# IO_board-ha-v2.net
KiCad netlist of a schematic drawn in EAGLE
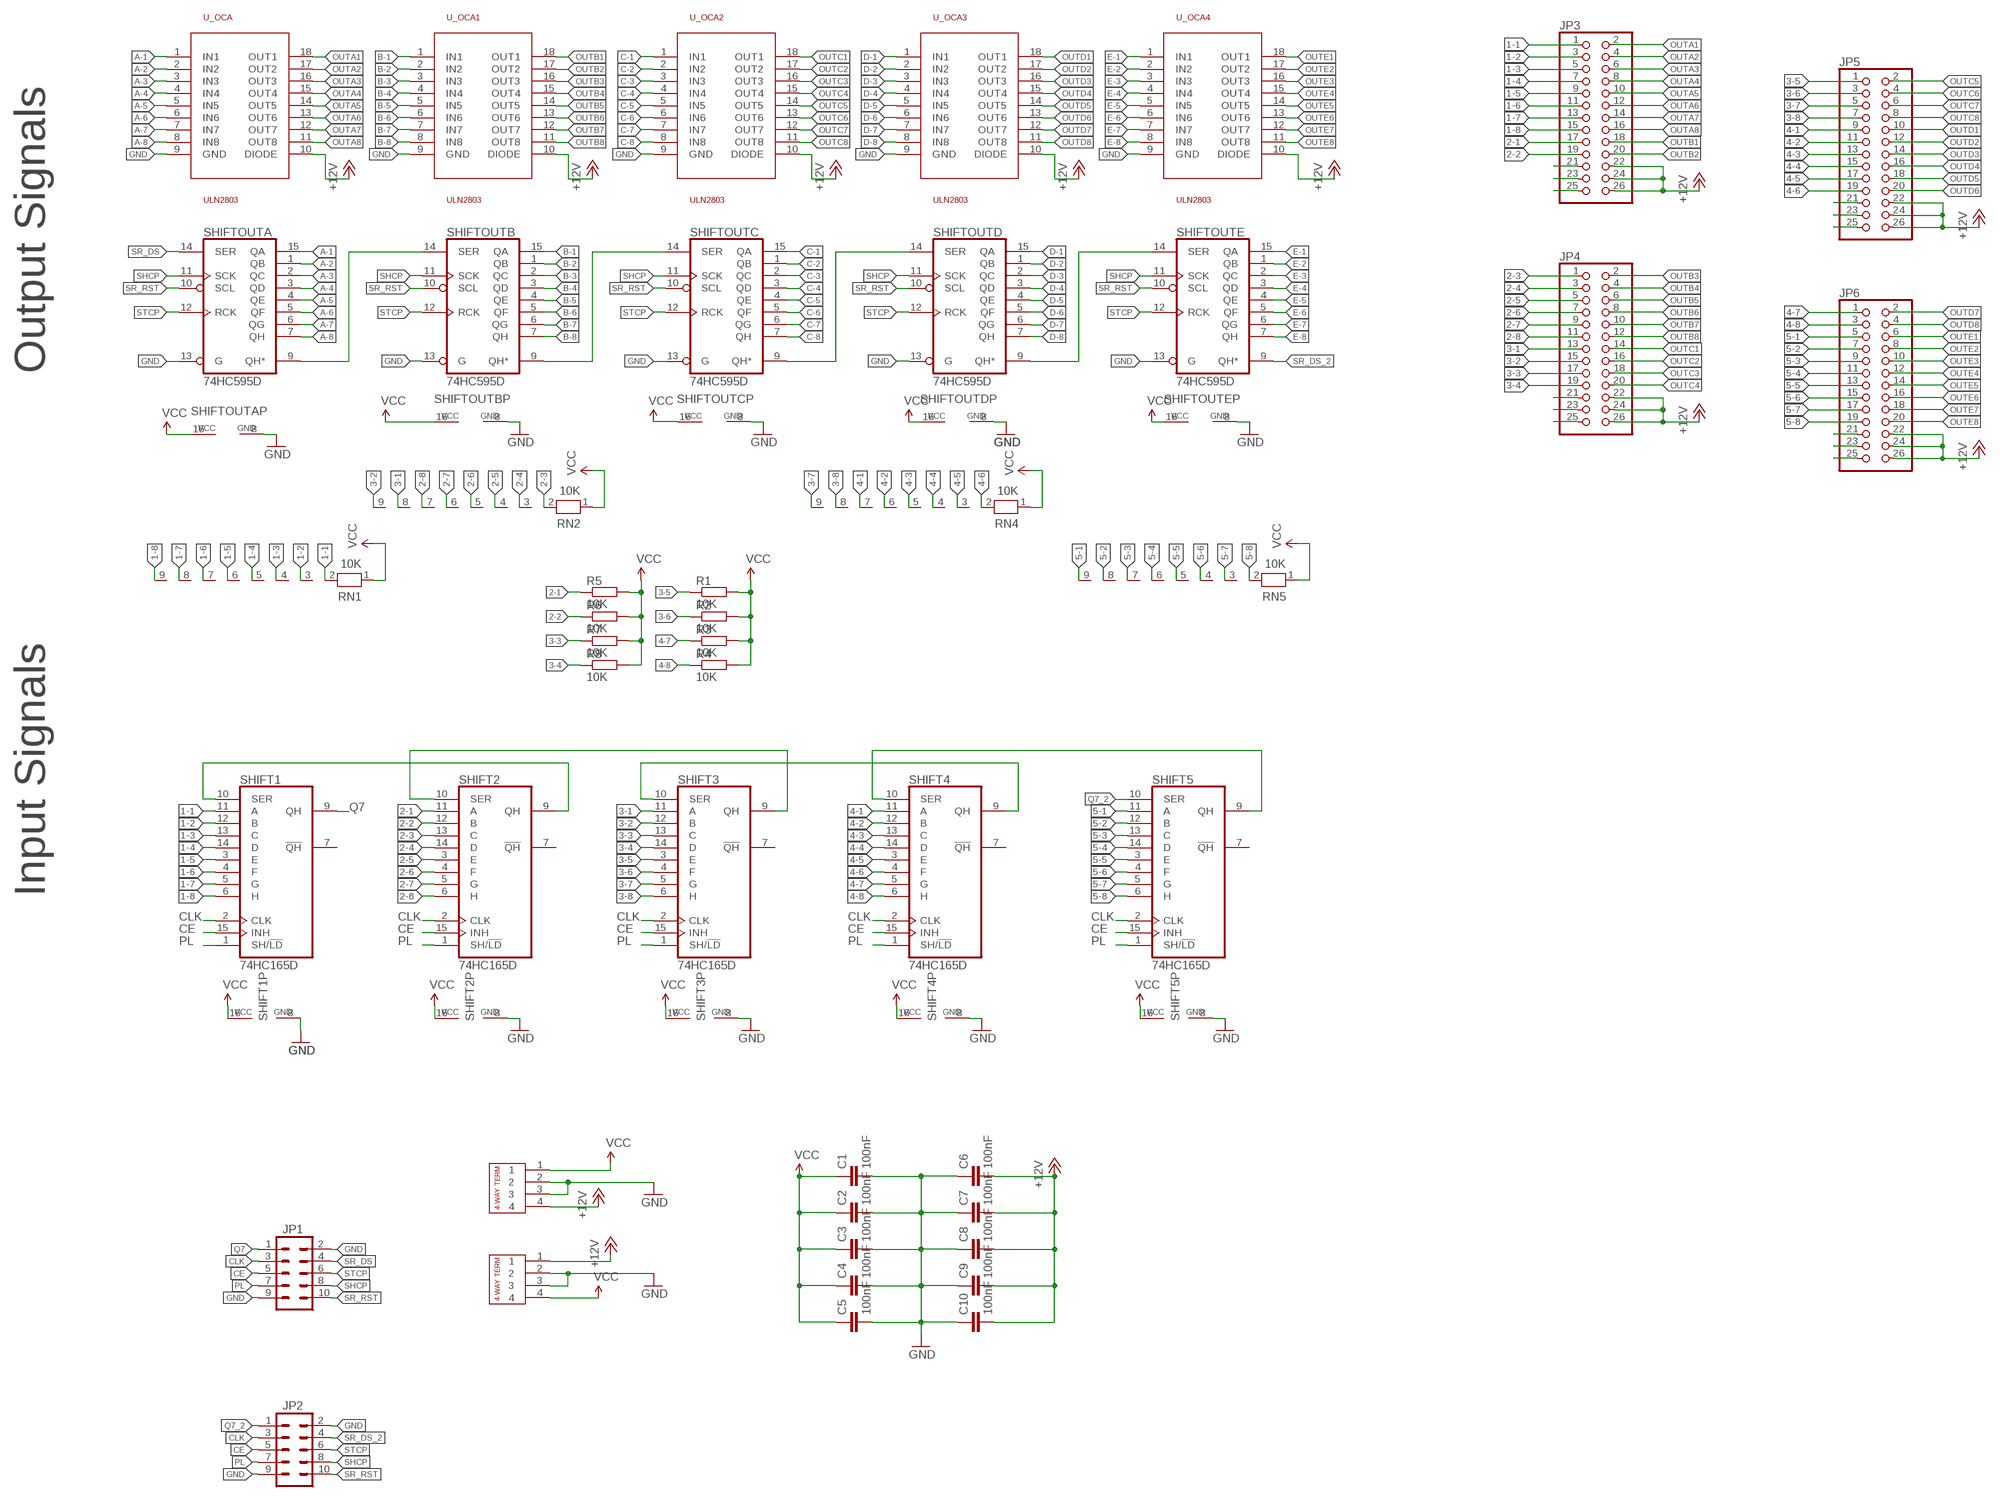
[diagram p0: schematic, sheet 1]

(export (version "E")
  (design (tool "Eeschema 10.0.6"))
  (components
    (comp (ref "C1")
      (value "100nF")
      (footprint "eagle-import:C0805")
      (libsource (lib "eagle-import") (part "C-EUC0805"))
    )
    (comp (ref "C2")
      (value "100nF")
      (footprint "eagle-import:C0805")
      (libsource (lib "eagle-import") (part "C-EUC0805"))
    )
    (comp (ref "C3")
      (value "100nF")
      (footprint "eagle-import:C0805")
      (libsource (lib "eagle-import") (part "C-EUC0805"))
    )
    (comp (ref "C4")
      (value "100nF")
      (footprint "eagle-import:C0805")
      (libsource (lib "eagle-import") (part "C-EUC0805"))
    )
    (comp (ref "C5")
      (value "100nF")
      (footprint "eagle-import:C0805")
      (libsource (lib "eagle-import") (part "C-EUC0805"))
    )
    (comp (ref "C6")
      (value "100nF")
      (footprint "eagle-import:C0805")
      (libsource (lib "eagle-import") (part "C-EUC0805"))
    )
    (comp (ref "C7")
      (value "100nF")
      (footprint "eagle-import:C0805")
      (libsource (lib "eagle-import") (part "C-EUC0805"))
    )
    (comp (ref "C8")
      (value "100nF")
      (footprint "eagle-import:C0805")
      (libsource (lib "eagle-import") (part "C-EUC0805"))
    )
    (comp (ref "C9")
      (value "100nF")
      (footprint "eagle-import:C0805")
      (libsource (lib "eagle-import") (part "C-EUC0805"))
    )
    (comp (ref "C10")
      (value "100nF")
      (footprint "eagle-import:C0805")
      (libsource (lib "eagle-import") (part "C-EUC0805"))
    )
    (comp (ref "J1")
      (value "4-PIN-CON-1759017")
      (footprint "eagle-import:4-PIN-CON-1759017")
      (libsource (lib "eagle-import") (part "4-PIN-CON-1759017"))
    )
    (comp (ref "J2")
      (value "4-PIN-CON-1759017")
      (footprint "eagle-import:4-PIN-CON-1759017")
      (libsource (lib "eagle-import") (part "4-PIN-CON-1759017"))
    )
    (comp (ref "JP1")
      (value "M05X2SHD")
      (footprint "eagle-import:2X5-SHROUDED")
      (libsource (lib "eagle-import") (part "M05X2SHD"))
    )
    (comp (ref "JP2")
      (value "M05X2SHD")
      (footprint "eagle-import:2X5-SHROUDED")
      (libsource (lib "eagle-import") (part "M05X2SHD"))
    )
    (comp (ref "JP3")
      (value "PINHD-2X13")
      (footprint "eagle-import:2X13")
      (libsource (lib "eagle-import") (part "PINHD-2X13"))
    )
    (comp (ref "JP4")
      (value "PINHD-2X13")
      (footprint "eagle-import:2X13")
      (libsource (lib "eagle-import") (part "PINHD-2X13"))
    )
    (comp (ref "JP5")
      (value "PINHD-2X13")
      (footprint "eagle-import:2X13")
      (libsource (lib "eagle-import") (part "PINHD-2X13"))
    )
    (comp (ref "JP6")
      (value "PINHD-2X13")
      (footprint "eagle-import:2X13")
      (libsource (lib "eagle-import") (part "PINHD-2X13"))
    )
    (comp (ref "R1")
      (value "10K")
      (footprint "eagle-import:R0603")
      (libsource (lib "eagle-import") (part "R-EU_R0603"))
    )
    (comp (ref "R2")
      (value "10K")
      (footprint "eagle-import:R0603")
      (libsource (lib "eagle-import") (part "R-EU_R0603"))
    )
    (comp (ref "R3")
      (value "10K")
      (footprint "eagle-import:R0603")
      (libsource (lib "eagle-import") (part "R-EU_R0603"))
    )
    (comp (ref "R4")
      (value "10K")
      (footprint "eagle-import:R0603")
      (libsource (lib "eagle-import") (part "R-EU_R0603"))
    )
    (comp (ref "R5")
      (value "10K")
      (footprint "eagle-import:R0603")
      (libsource (lib "eagle-import") (part "R-EU_R0603"))
    )
    (comp (ref "R6")
      (value "10K")
      (footprint "eagle-import:R0603")
      (libsource (lib "eagle-import") (part "R-EU_R0603"))
    )
    (comp (ref "R7")
      (value "10K")
      (footprint "eagle-import:R0603")
      (libsource (lib "eagle-import") (part "R-EU_R0603"))
    )
    (comp (ref "R8")
      (value "10K")
      (footprint "eagle-import:R0603")
      (libsource (lib "eagle-import") (part "R-EU_R0603"))
    )
    (comp (ref "RN1")
      (value "10K")
      (footprint "eagle-import:RN-9")
      (libsource (lib "eagle-import") (part "RN08"))
    )
    (comp (ref "RN2")
      (value "10K")
      (footprint "eagle-import:RN-9")
      (libsource (lib "eagle-import") (part "RN08"))
    )
    (comp (ref "RN4")
      (value "10K")
      (footprint "eagle-import:RN-9")
      (libsource (lib "eagle-import") (part "RN08"))
    )
    (comp (ref "RN5")
      (value "10K")
      (footprint "eagle-import:RN-9")
      (libsource (lib "eagle-import") (part "RN08"))
    )
    (comp (ref "SHIFT1")
      (value "74HC165D")
      (footprint "eagle-import:SO16")
      (libsource (lib "eagle-import") (part "74165DHC"))
    )
    (comp (ref "SHIFT2")
      (value "74HC165D")
      (footprint "eagle-import:SO16")
      (libsource (lib "eagle-import") (part "74165DHC"))
    )
    (comp (ref "SHIFT3")
      (value "74HC165D")
      (footprint "eagle-import:SO16")
      (libsource (lib "eagle-import") (part "74165DHC"))
    )
    (comp (ref "SHIFT4")
      (value "74HC165D")
      (footprint "eagle-import:SO16")
      (libsource (lib "eagle-import") (part "74165DHC"))
    )
    (comp (ref "SHIFT5")
      (value "74HC165D")
      (footprint "eagle-import:SO16")
      (libsource (lib "eagle-import") (part "74165DHC"))
    )
    (comp (ref "SHIFTOUTA")
      (value "74HC595D")
      (footprint "eagle-import:SO16")
      (libsource (lib "eagle-import") (part "74595DHC"))
    )
    (comp (ref "SHIFTOUTB")
      (value "74HC595D")
      (footprint "eagle-import:SO16")
      (libsource (lib "eagle-import") (part "74595DHC"))
    )
    (comp (ref "SHIFTOUTC")
      (value "74HC595D")
      (footprint "eagle-import:SO16")
      (libsource (lib "eagle-import") (part "74595DHC"))
    )
    (comp (ref "SHIFTOUTD")
      (value "74HC595D")
      (footprint "eagle-import:SO16")
      (libsource (lib "eagle-import") (part "74595DHC"))
    )
    (comp (ref "SHIFTOUTE")
      (value "74HC595D")
      (footprint "eagle-import:SO16")
      (libsource (lib "eagle-import") (part "74595DHC"))
    )
    (comp (ref "U_OCA")
      (value "ULN2803")
      (footprint "eagle-import:SO18L")
      (libsource (lib "eagle-import") (part "ULN2803"))
    )
    (comp (ref "U_OCA1")
      (value "ULN2803")
      (footprint "eagle-import:SO18L")
      (libsource (lib "eagle-import") (part "ULN2803"))
    )
    (comp (ref "U_OCA2")
      (value "ULN2803")
      (footprint "eagle-import:SO18L")
      (libsource (lib "eagle-import") (part "ULN2803"))
    )
    (comp (ref "U_OCA3")
      (value "ULN2803")
      (footprint "eagle-import:SO18L")
      (libsource (lib "eagle-import") (part "ULN2803"))
    )
    (comp (ref "U_OCA4")
      (value "ULN2803")
      (footprint "eagle-import:SO18L")
      (libsource (lib "eagle-import") (part "ULN2803"))
    )
  )
  (nets
    (net (code "1") (name "+12V") (class "Default")
      (node (ref "C10") (pin "2") (pinfunction "2_2") (pintype "passive"))
      (node (ref "C6") (pin "2") (pinfunction "2_2") (pintype "passive"))
      (node (ref "C7") (pin "2") (pinfunction "2_2") (pintype "passive"))
      (node (ref "C8") (pin "2") (pinfunction "2_2") (pintype "passive"))
      (node (ref "C9") (pin "2") (pinfunction "2_2") (pintype "passive"))
      (node (ref "J1") (pin "4") (pinfunction "4_4") (pintype "bidirectional"))
      (node (ref "J2") (pin "1") (pinfunction "1_1") (pintype "bidirectional"))
      (node (ref "JP3") (pin "22") (pinfunction "22_22") (pintype "passive"))
      (node (ref "JP3") (pin "24") (pinfunction "24_24") (pintype "passive"))
      (node (ref "JP3") (pin "26") (pinfunction "26_26") (pintype "passive"))
      (node (ref "JP4") (pin "22") (pinfunction "22_22") (pintype "passive"))
      (node (ref "JP4") (pin "24") (pinfunction "24_24") (pintype "passive"))
      (node (ref "JP4") (pin "26") (pinfunction "26_26") (pintype "passive"))
      (node (ref "JP5") (pin "22") (pinfunction "22_22") (pintype "passive"))
      (node (ref "JP5") (pin "24") (pinfunction "24_24") (pintype "passive"))
      (node (ref "JP5") (pin "26") (pinfunction "26_26") (pintype "passive"))
      (node (ref "JP6") (pin "22") (pinfunction "22_22") (pintype "passive"))
      (node (ref "JP6") (pin "24") (pinfunction "24_24") (pintype "passive"))
      (node (ref "JP6") (pin "26") (pinfunction "26_26") (pintype "passive"))
      (node (ref "U_OCA") (pin "10") (pinfunction "DIODE_10") (pintype "power_in"))
      (node (ref "U_OCA1") (pin "10") (pinfunction "DIODE_10") (pintype "power_in"))
      (node (ref "U_OCA2") (pin "10") (pinfunction "DIODE_10") (pintype "power_in"))
      (node (ref "U_OCA3") (pin "10") (pinfunction "DIODE_10") (pintype "power_in"))
      (node (ref "U_OCA4") (pin "10") (pinfunction "DIODE_10") (pintype "power_in"))
    )
    (net (code "2") (name "1-1") (class "Default")
      (node (ref "JP3") (pin "1") (pinfunction "1_1") (pintype "passive"))
      (node (ref "RN1") (pin "2") (pinfunction "2_2") (pintype "passive"))
      (node (ref "SHIFT1") (pin "11") (pinfunction "A_11") (pintype "input"))
    )
    (net (code "3") (name "1-2") (class "Default")
      (node (ref "JP3") (pin "3") (pinfunction "3_3") (pintype "passive"))
      (node (ref "RN1") (pin "3") (pinfunction "3_3") (pintype "passive"))
      (node (ref "SHIFT1") (pin "12") (pinfunction "B_12") (pintype "input"))
    )
    (net (code "4") (name "1-3") (class "Default")
      (node (ref "JP3") (pin "5") (pinfunction "5_5") (pintype "passive"))
      (node (ref "RN1") (pin "4") (pinfunction "4_4") (pintype "passive"))
      (node (ref "SHIFT1") (pin "13") (pinfunction "C_13") (pintype "input"))
    )
    (net (code "5") (name "1-4") (class "Default")
      (node (ref "JP3") (pin "7") (pinfunction "7_7") (pintype "passive"))
      (node (ref "RN1") (pin "5") (pinfunction "5_5") (pintype "passive"))
      (node (ref "SHIFT1") (pin "14") (pinfunction "D_14") (pintype "input"))
    )
    (net (code "6") (name "1-5") (class "Default")
      (node (ref "JP3") (pin "9") (pinfunction "9_9") (pintype "passive"))
      (node (ref "RN1") (pin "6") (pinfunction "6_6") (pintype "passive"))
      (node (ref "SHIFT1") (pin "3") (pinfunction "E_3") (pintype "input"))
    )
    (net (code "7") (name "1-6") (class "Default")
      (node (ref "JP3") (pin "11") (pinfunction "11_11") (pintype "passive"))
      (node (ref "RN1") (pin "7") (pinfunction "7_7") (pintype "passive"))
      (node (ref "SHIFT1") (pin "4") (pinfunction "F_4") (pintype "input"))
    )
    (net (code "8") (name "1-7") (class "Default")
      (node (ref "JP3") (pin "13") (pinfunction "13_13") (pintype "passive"))
      (node (ref "RN1") (pin "8") (pinfunction "8_8") (pintype "passive"))
      (node (ref "SHIFT1") (pin "5") (pinfunction "G_5") (pintype "input"))
    )
    (net (code "9") (name "1-8") (class "Default")
      (node (ref "JP3") (pin "15") (pinfunction "15_15") (pintype "passive"))
      (node (ref "RN1") (pin "9") (pinfunction "9_9") (pintype "passive"))
      (node (ref "SHIFT1") (pin "6") (pinfunction "H_6") (pintype "input"))
    )
    (net (code "10") (name "2-1") (class "Default")
      (node (ref "JP3") (pin "17") (pinfunction "17_17") (pintype "passive"))
      (node (ref "R5") (pin "1") (pinfunction "1_1") (pintype "passive"))
      (node (ref "SHIFT2") (pin "11") (pinfunction "A_11") (pintype "input"))
    )
    (net (code "11") (name "2-2") (class "Default")
      (node (ref "JP3") (pin "19") (pinfunction "19_19") (pintype "passive"))
      (node (ref "R6") (pin "1") (pinfunction "1_1") (pintype "passive"))
      (node (ref "SHIFT2") (pin "12") (pinfunction "B_12") (pintype "input"))
    )
    (net (code "12") (name "2-3") (class "Default")
      (node (ref "JP4") (pin "1") (pinfunction "1_1") (pintype "passive"))
      (node (ref "RN2") (pin "2") (pinfunction "2_2") (pintype "passive"))
      (node (ref "SHIFT2") (pin "13") (pinfunction "C_13") (pintype "input"))
    )
    (net (code "13") (name "2-4") (class "Default")
      (node (ref "JP4") (pin "3") (pinfunction "3_3") (pintype "passive"))
      (node (ref "RN2") (pin "3") (pinfunction "3_3") (pintype "passive"))
      (node (ref "SHIFT2") (pin "14") (pinfunction "D_14") (pintype "input"))
    )
    (net (code "14") (name "2-5") (class "Default")
      (node (ref "JP4") (pin "5") (pinfunction "5_5") (pintype "passive"))
      (node (ref "RN2") (pin "4") (pinfunction "4_4") (pintype "passive"))
      (node (ref "SHIFT2") (pin "3") (pinfunction "E_3") (pintype "input"))
    )
    (net (code "15") (name "2-6") (class "Default")
      (node (ref "JP4") (pin "7") (pinfunction "7_7") (pintype "passive"))
      (node (ref "RN2") (pin "5") (pinfunction "5_5") (pintype "passive"))
      (node (ref "SHIFT2") (pin "4") (pinfunction "F_4") (pintype "input"))
    )
    (net (code "16") (name "2-7") (class "Default")
      (node (ref "JP4") (pin "9") (pinfunction "9_9") (pintype "passive"))
      (node (ref "RN2") (pin "6") (pinfunction "6_6") (pintype "passive"))
      (node (ref "SHIFT2") (pin "5") (pinfunction "G_5") (pintype "input"))
    )
    (net (code "17") (name "2-8") (class "Default")
      (node (ref "JP4") (pin "11") (pinfunction "11_11") (pintype "passive"))
      (node (ref "RN2") (pin "7") (pinfunction "7_7") (pintype "passive"))
      (node (ref "SHIFT2") (pin "6") (pinfunction "H_6") (pintype "input"))
    )
    (net (code "18") (name "3-1") (class "Default")
      (node (ref "JP4") (pin "13") (pinfunction "13_13") (pintype "passive"))
      (node (ref "RN2") (pin "8") (pinfunction "8_8") (pintype "passive"))
      (node (ref "SHIFT3") (pin "11") (pinfunction "A_11") (pintype "input"))
    )
    (net (code "19") (name "3-2") (class "Default")
      (node (ref "JP4") (pin "15") (pinfunction "15_15") (pintype "passive"))
      (node (ref "RN2") (pin "9") (pinfunction "9_9") (pintype "passive"))
      (node (ref "SHIFT3") (pin "12") (pinfunction "B_12") (pintype "input"))
    )
    (net (code "20") (name "3-3") (class "Default")
      (node (ref "JP4") (pin "17") (pinfunction "17_17") (pintype "passive"))
      (node (ref "R7") (pin "1") (pinfunction "1_1") (pintype "passive"))
      (node (ref "SHIFT3") (pin "13") (pinfunction "C_13") (pintype "input"))
    )
    (net (code "21") (name "3-4") (class "Default")
      (node (ref "JP4") (pin "19") (pinfunction "19_19") (pintype "passive"))
      (node (ref "R8") (pin "1") (pinfunction "1_1") (pintype "passive"))
      (node (ref "SHIFT3") (pin "14") (pinfunction "D_14") (pintype "input"))
    )
    (net (code "22") (name "3-5") (class "Default")
      (node (ref "JP5") (pin "1") (pinfunction "1_1") (pintype "passive"))
      (node (ref "R1") (pin "1") (pinfunction "1_1") (pintype "passive"))
      (node (ref "SHIFT3") (pin "3") (pinfunction "E_3") (pintype "input"))
    )
    (net (code "23") (name "3-6") (class "Default")
      (node (ref "JP5") (pin "3") (pinfunction "3_3") (pintype "passive"))
      (node (ref "R2") (pin "1") (pinfunction "1_1") (pintype "passive"))
      (node (ref "SHIFT3") (pin "4") (pinfunction "F_4") (pintype "input"))
    )
    (net (code "24") (name "3-7") (class "Default")
      (node (ref "JP5") (pin "5") (pinfunction "5_5") (pintype "passive"))
      (node (ref "RN4") (pin "9") (pinfunction "9_9") (pintype "passive"))
      (node (ref "SHIFT3") (pin "5") (pinfunction "G_5") (pintype "input"))
    )
    (net (code "25") (name "3-8") (class "Default")
      (node (ref "JP5") (pin "7") (pinfunction "7_7") (pintype "passive"))
      (node (ref "RN4") (pin "8") (pinfunction "8_8") (pintype "passive"))
      (node (ref "SHIFT3") (pin "6") (pinfunction "H_6") (pintype "input"))
    )
    (net (code "26") (name "4-1") (class "Default")
      (node (ref "JP5") (pin "9") (pinfunction "9_9") (pintype "passive"))
      (node (ref "RN4") (pin "7") (pinfunction "7_7") (pintype "passive"))
      (node (ref "SHIFT4") (pin "11") (pinfunction "A_11") (pintype "input"))
    )
    (net (code "27") (name "4-2") (class "Default")
      (node (ref "JP5") (pin "11") (pinfunction "11_11") (pintype "passive"))
      (node (ref "RN4") (pin "6") (pinfunction "6_6") (pintype "passive"))
      (node (ref "SHIFT4") (pin "12") (pinfunction "B_12") (pintype "input"))
    )
    (net (code "28") (name "4-3") (class "Default")
      (node (ref "JP5") (pin "13") (pinfunction "13_13") (pintype "passive"))
      (node (ref "RN4") (pin "5") (pinfunction "5_5") (pintype "passive"))
      (node (ref "SHIFT4") (pin "13") (pinfunction "C_13") (pintype "input"))
    )
    (net (code "29") (name "4-4") (class "Default")
      (node (ref "JP5") (pin "15") (pinfunction "15_15") (pintype "passive"))
      (node (ref "RN4") (pin "4") (pinfunction "4_4") (pintype "passive"))
      (node (ref "SHIFT4") (pin "14") (pinfunction "D_14") (pintype "input"))
    )
    (net (code "30") (name "4-5") (class "Default")
      (node (ref "JP5") (pin "17") (pinfunction "17_17") (pintype "passive"))
      (node (ref "RN4") (pin "3") (pinfunction "3_3") (pintype "passive"))
      (node (ref "SHIFT4") (pin "3") (pinfunction "E_3") (pintype "input"))
    )
    (net (code "31") (name "4-6") (class "Default")
      (node (ref "JP5") (pin "19") (pinfunction "19_19") (pintype "passive"))
      (node (ref "RN4") (pin "2") (pinfunction "2_2") (pintype "passive"))
      (node (ref "SHIFT4") (pin "4") (pinfunction "F_4") (pintype "input"))
    )
    (net (code "32") (name "4-7") (class "Default")
      (node (ref "JP6") (pin "1") (pinfunction "1_1") (pintype "passive"))
      (node (ref "R3") (pin "1") (pinfunction "1_1") (pintype "passive"))
      (node (ref "SHIFT4") (pin "5") (pinfunction "G_5") (pintype "input"))
    )
    (net (code "33") (name "4-8") (class "Default")
      (node (ref "JP6") (pin "3") (pinfunction "3_3") (pintype "passive"))
      (node (ref "R4") (pin "1") (pinfunction "1_1") (pintype "passive"))
      (node (ref "SHIFT4") (pin "6") (pinfunction "H_6") (pintype "input"))
    )
    (net (code "34") (name "5-1") (class "Default")
      (node (ref "JP6") (pin "5") (pinfunction "5_5") (pintype "passive"))
      (node (ref "RN5") (pin "9") (pinfunction "9_9") (pintype "passive"))
      (node (ref "SHIFT5") (pin "11") (pinfunction "A_11") (pintype "input"))
    )
    (net (code "35") (name "5-2") (class "Default")
      (node (ref "JP6") (pin "7") (pinfunction "7_7") (pintype "passive"))
      (node (ref "RN5") (pin "8") (pinfunction "8_8") (pintype "passive"))
      (node (ref "SHIFT5") (pin "12") (pinfunction "B_12") (pintype "input"))
    )
    (net (code "36") (name "5-3") (class "Default")
      (node (ref "JP6") (pin "9") (pinfunction "9_9") (pintype "passive"))
      (node (ref "RN5") (pin "7") (pinfunction "7_7") (pintype "passive"))
      (node (ref "SHIFT5") (pin "13") (pinfunction "C_13") (pintype "input"))
    )
    (net (code "37") (name "5-4") (class "Default")
      (node (ref "JP6") (pin "11") (pinfunction "11_11") (pintype "passive"))
      (node (ref "RN5") (pin "6") (pinfunction "6_6") (pintype "passive"))
      (node (ref "SHIFT5") (pin "14") (pinfunction "D_14") (pintype "input"))
    )
    (net (code "38") (name "5-5") (class "Default")
      (node (ref "JP6") (pin "13") (pinfunction "13_13") (pintype "passive"))
      (node (ref "RN5") (pin "5") (pinfunction "5_5") (pintype "passive"))
      (node (ref "SHIFT5") (pin "3") (pinfunction "E_3") (pintype "input"))
    )
    (net (code "39") (name "5-6") (class "Default")
      (node (ref "JP6") (pin "15") (pinfunction "15_15") (pintype "passive"))
      (node (ref "RN5") (pin "4") (pinfunction "4_4") (pintype "passive"))
      (node (ref "SHIFT5") (pin "4") (pinfunction "F_4") (pintype "input"))
    )
    (net (code "40") (name "5-7") (class "Default")
      (node (ref "JP6") (pin "17") (pinfunction "17_17") (pintype "passive"))
      (node (ref "RN5") (pin "3") (pinfunction "3_3") (pintype "passive"))
      (node (ref "SHIFT5") (pin "5") (pinfunction "G_5") (pintype "input"))
    )
    (net (code "41") (name "5-8") (class "Default")
      (node (ref "JP6") (pin "19") (pinfunction "19_19") (pintype "passive"))
      (node (ref "RN5") (pin "2") (pinfunction "2_2") (pintype "passive"))
      (node (ref "SHIFT5") (pin "6") (pinfunction "H_6") (pintype "input"))
    )
    (net (code "42") (name "A-1") (class "Default")
      (node (ref "SHIFTOUTA") (pin "15") (pinfunction "QA_15") (pintype "tri_state"))
      (node (ref "U_OCA") (pin "1") (pinfunction "IN1_1") (pintype "input"))
    )
    (net (code "43") (name "A-2") (class "Default")
      (node (ref "SHIFTOUTA") (pin "1") (pinfunction "QB_1") (pintype "tri_state"))
      (node (ref "U_OCA") (pin "2") (pinfunction "IN2_2") (pintype "input"))
    )
    (net (code "44") (name "A-3") (class "Default")
      (node (ref "SHIFTOUTA") (pin "2") (pinfunction "QC_2") (pintype "tri_state"))
      (node (ref "U_OCA") (pin "3") (pinfunction "IN3_3") (pintype "input"))
    )
    (net (code "45") (name "A-4") (class "Default")
      (node (ref "SHIFTOUTA") (pin "3") (pinfunction "QD_3") (pintype "tri_state"))
      (node (ref "U_OCA") (pin "4") (pinfunction "IN4_4") (pintype "input"))
    )
    (net (code "46") (name "A-5") (class "Default")
      (node (ref "SHIFTOUTA") (pin "4") (pinfunction "QE_4") (pintype "tri_state"))
      (node (ref "U_OCA") (pin "5") (pinfunction "IN5_5") (pintype "input"))
    )
    (net (code "47") (name "A-6") (class "Default")
      (node (ref "SHIFTOUTA") (pin "5") (pinfunction "QF_5") (pintype "tri_state"))
      (node (ref "U_OCA") (pin "6") (pinfunction "IN6_6") (pintype "input"))
    )
    (net (code "48") (name "A-7") (class "Default")
      (node (ref "SHIFTOUTA") (pin "6") (pinfunction "QG_6") (pintype "tri_state"))
      (node (ref "U_OCA") (pin "7") (pinfunction "IN7_7") (pintype "input"))
    )
    (net (code "49") (name "A-8") (class "Default")
      (node (ref "SHIFTOUTA") (pin "7") (pinfunction "QH_7") (pintype "tri_state"))
      (node (ref "U_OCA") (pin "8") (pinfunction "IN8_8") (pintype "input"))
    )
    (net (code "50") (name "B-1") (class "Default")
      (node (ref "SHIFTOUTB") (pin "15") (pinfunction "QA_15") (pintype "tri_state"))
      (node (ref "U_OCA1") (pin "1") (pinfunction "IN1_1") (pintype "input"))
    )
    (net (code "51") (name "B-2") (class "Default")
      (node (ref "SHIFTOUTB") (pin "1") (pinfunction "QB_1") (pintype "tri_state"))
      (node (ref "U_OCA1") (pin "2") (pinfunction "IN2_2") (pintype "input"))
    )
    (net (code "52") (name "B-3") (class "Default")
      (node (ref "SHIFTOUTB") (pin "2") (pinfunction "QC_2") (pintype "tri_state"))
      (node (ref "U_OCA1") (pin "3") (pinfunction "IN3_3") (pintype "input"))
    )
    (net (code "53") (name "B-4") (class "Default")
      (node (ref "SHIFTOUTB") (pin "3") (pinfunction "QD_3") (pintype "tri_state"))
      (node (ref "U_OCA1") (pin "4") (pinfunction "IN4_4") (pintype "input"))
    )
    (net (code "54") (name "B-5") (class "Default")
      (node (ref "SHIFTOUTB") (pin "4") (pinfunction "QE_4") (pintype "tri_state"))
      (node (ref "U_OCA1") (pin "5") (pinfunction "IN5_5") (pintype "input"))
    )
    (net (code "55") (name "B-6") (class "Default")
      (node (ref "SHIFTOUTB") (pin "5") (pinfunction "QF_5") (pintype "tri_state"))
      (node (ref "U_OCA1") (pin "6") (pinfunction "IN6_6") (pintype "input"))
    )
    (net (code "56") (name "B-7") (class "Default")
      (node (ref "SHIFTOUTB") (pin "6") (pinfunction "QG_6") (pintype "tri_state"))
      (node (ref "U_OCA1") (pin "7") (pinfunction "IN7_7") (pintype "input"))
    )
    (net (code "57") (name "B-8") (class "Default")
      (node (ref "SHIFTOUTB") (pin "7") (pinfunction "QH_7") (pintype "tri_state"))
      (node (ref "U_OCA1") (pin "8") (pinfunction "IN8_8") (pintype "input"))
    )
    (net (code "58") (name "C-1") (class "Default")
      (node (ref "SHIFTOUTC") (pin "15") (pinfunction "QA_15") (pintype "tri_state"))
      (node (ref "U_OCA2") (pin "1") (pinfunction "IN1_1") (pintype "input"))
    )
    (net (code "59") (name "C-2") (class "Default")
      (node (ref "SHIFTOUTC") (pin "1") (pinfunction "QB_1") (pintype "tri_state"))
      (node (ref "U_OCA2") (pin "2") (pinfunction "IN2_2") (pintype "input"))
    )
    (net (code "60") (name "C-3") (class "Default")
      (node (ref "SHIFTOUTC") (pin "2") (pinfunction "QC_2") (pintype "tri_state"))
      (node (ref "U_OCA2") (pin "3") (pinfunction "IN3_3") (pintype "input"))
    )
    (net (code "61") (name "C-4") (class "Default")
      (node (ref "SHIFTOUTC") (pin "3") (pinfunction "QD_3") (pintype "tri_state"))
      (node (ref "U_OCA2") (pin "4") (pinfunction "IN4_4") (pintype "input"))
    )
    (net (code "62") (name "C-5") (class "Default")
      (node (ref "SHIFTOUTC") (pin "4") (pinfunction "QE_4") (pintype "tri_state"))
      (node (ref "U_OCA2") (pin "5") (pinfunction "IN5_5") (pintype "input"))
    )
    (net (code "63") (name "C-6") (class "Default")
      (node (ref "SHIFTOUTC") (pin "5") (pinfunction "QF_5") (pintype "tri_state"))
      (node (ref "U_OCA2") (pin "6") (pinfunction "IN6_6") (pintype "input"))
    )
    (net (code "64") (name "C-7") (class "Default")
      (node (ref "SHIFTOUTC") (pin "6") (pinfunction "QG_6") (pintype "tri_state"))
      (node (ref "U_OCA2") (pin "7") (pinfunction "IN7_7") (pintype "input"))
    )
    (net (code "65") (name "C-8") (class "Default")
      (node (ref "SHIFTOUTC") (pin "7") (pinfunction "QH_7") (pintype "tri_state"))
      (node (ref "U_OCA2") (pin "8") (pinfunction "IN8_8") (pintype "input"))
    )
    (net (code "66") (name "CE") (class "Default")
      (node (ref "JP1") (pin "5") (pinfunction "5_5") (pintype "passive"))
      (node (ref "JP2") (pin "5") (pinfunction "5_5") (pintype "passive"))
      (node (ref "SHIFT1") (pin "15") (pinfunction "INH_15") (pintype "input"))
      (node (ref "SHIFT2") (pin "15") (pinfunction "INH_15") (pintype "input"))
      (node (ref "SHIFT3") (pin "15") (pinfunction "INH_15") (pintype "input"))
      (node (ref "SHIFT4") (pin "15") (pinfunction "INH_15") (pintype "input"))
      (node (ref "SHIFT5") (pin "15") (pinfunction "INH_15") (pintype "input"))
    )
    (net (code "67") (name "CLK") (class "Default")
      (node (ref "JP1") (pin "3") (pinfunction "3_3") (pintype "passive"))
      (node (ref "JP2") (pin "3") (pinfunction "3_3") (pintype "passive"))
      (node (ref "SHIFT1") (pin "2") (pinfunction "CLK_2") (pintype "input"))
      (node (ref "SHIFT2") (pin "2") (pinfunction "CLK_2") (pintype "input"))
      (node (ref "SHIFT3") (pin "2") (pinfunction "CLK_2") (pintype "input"))
      (node (ref "SHIFT4") (pin "2") (pinfunction "CLK_2") (pintype "input"))
      (node (ref "SHIFT5") (pin "2") (pinfunction "CLK_2") (pintype "input"))
    )
    (net (code "68") (name "D-1") (class "Default")
      (node (ref "SHIFTOUTD") (pin "15") (pinfunction "QA_15") (pintype "tri_state"))
      (node (ref "U_OCA3") (pin "1") (pinfunction "IN1_1") (pintype "input"))
    )
    (net (code "69") (name "D-2") (class "Default")
      (node (ref "SHIFTOUTD") (pin "1") (pinfunction "QB_1") (pintype "tri_state"))
      (node (ref "U_OCA3") (pin "2") (pinfunction "IN2_2") (pintype "input"))
    )
    (net (code "70") (name "D-3") (class "Default")
      (node (ref "SHIFTOUTD") (pin "2") (pinfunction "QC_2") (pintype "tri_state"))
      (node (ref "U_OCA3") (pin "3") (pinfunction "IN3_3") (pintype "input"))
    )
    (net (code "71") (name "D-4") (class "Default")
      (node (ref "SHIFTOUTD") (pin "3") (pinfunction "QD_3") (pintype "tri_state"))
      (node (ref "U_OCA3") (pin "4") (pinfunction "IN4_4") (pintype "input"))
    )
    (net (code "72") (name "D-5") (class "Default")
      (node (ref "SHIFTOUTD") (pin "4") (pinfunction "QE_4") (pintype "tri_state"))
      (node (ref "U_OCA3") (pin "5") (pinfunction "IN5_5") (pintype "input"))
    )
    (net (code "73") (name "D-6") (class "Default")
      (node (ref "SHIFTOUTD") (pin "5") (pinfunction "QF_5") (pintype "tri_state"))
      (node (ref "U_OCA3") (pin "6") (pinfunction "IN6_6") (pintype "input"))
    )
    (net (code "74") (name "D-7") (class "Default")
      (node (ref "SHIFTOUTD") (pin "6") (pinfunction "QG_6") (pintype "tri_state"))
      (node (ref "U_OCA3") (pin "7") (pinfunction "IN7_7") (pintype "input"))
    )
    (net (code "75") (name "D-8") (class "Default")
      (node (ref "SHIFTOUTD") (pin "7") (pinfunction "QH_7") (pintype "tri_state"))
      (node (ref "U_OCA3") (pin "8") (pinfunction "IN8_8") (pintype "input"))
    )
    (net (code "76") (name "E-1") (class "Default")
      (node (ref "SHIFTOUTE") (pin "15") (pinfunction "QA_15") (pintype "tri_state"))
      (node (ref "U_OCA4") (pin "1") (pinfunction "IN1_1") (pintype "input"))
    )
    (net (code "77") (name "E-2") (class "Default")
      (node (ref "SHIFTOUTE") (pin "1") (pinfunction "QB_1") (pintype "tri_state"))
      (node (ref "U_OCA4") (pin "2") (pinfunction "IN2_2") (pintype "input"))
    )
    (net (code "78") (name "E-3") (class "Default")
      (node (ref "SHIFTOUTE") (pin "2") (pinfunction "QC_2") (pintype "tri_state"))
      (node (ref "U_OCA4") (pin "3") (pinfunction "IN3_3") (pintype "input"))
    )
    (net (code "79") (name "E-4") (class "Default")
      (node (ref "SHIFTOUTE") (pin "3") (pinfunction "QD_3") (pintype "tri_state"))
      (node (ref "U_OCA4") (pin "4") (pinfunction "IN4_4") (pintype "input"))
    )
    (net (code "80") (name "E-5") (class "Default")
      (node (ref "SHIFTOUTE") (pin "4") (pinfunction "QE_4") (pintype "tri_state"))
      (node (ref "U_OCA4") (pin "5") (pinfunction "IN5_5") (pintype "input"))
    )
    (net (code "81") (name "E-6") (class "Default")
      (node (ref "SHIFTOUTE") (pin "5") (pinfunction "QF_5") (pintype "tri_state"))
      (node (ref "U_OCA4") (pin "6") (pinfunction "IN6_6") (pintype "input"))
    )
    (net (code "82") (name "E-7") (class "Default")
      (node (ref "SHIFTOUTE") (pin "6") (pinfunction "QG_6") (pintype "tri_state"))
      (node (ref "U_OCA4") (pin "7") (pinfunction "IN7_7") (pintype "input"))
    )
    (net (code "83") (name "E-8") (class "Default")
      (node (ref "SHIFTOUTE") (pin "7") (pinfunction "QH_7") (pintype "tri_state"))
      (node (ref "U_OCA4") (pin "8") (pinfunction "IN8_8") (pintype "input"))
    )
    (net (code "84") (name "GND") (class "Default")
      (node (ref "C1") (pin "2") (pinfunction "2_2") (pintype "passive"))
      (node (ref "C10") (pin "1") (pinfunction "1_1") (pintype "passive"))
      (node (ref "C2") (pin "2") (pinfunction "2_2") (pintype "passive"))
      (node (ref "C3") (pin "2") (pinfunction "2_2") (pintype "passive"))
      (node (ref "C4") (pin "2") (pinfunction "2_2") (pintype "passive"))
      (node (ref "C5") (pin "2") (pinfunction "2_2") (pintype "passive"))
      (node (ref "C6") (pin "1") (pinfunction "1_1") (pintype "passive"))
      (node (ref "C7") (pin "1") (pinfunction "1_1") (pintype "passive"))
      (node (ref "C8") (pin "1") (pinfunction "1_1") (pintype "passive"))
      (node (ref "C9") (pin "1") (pinfunction "1_1") (pintype "passive"))
      (node (ref "J1") (pin "2") (pinfunction "2_2") (pintype "bidirectional"))
      (node (ref "J1") (pin "3") (pinfunction "3_3") (pintype "bidirectional"))
      (node (ref "J2") (pin "2") (pinfunction "2_2") (pintype "bidirectional"))
      (node (ref "J2") (pin "3") (pinfunction "3_3") (pintype "bidirectional"))
      (node (ref "JP1") (pin "2") (pinfunction "2_2") (pintype "passive"))
      (node (ref "JP1") (pin "9") (pinfunction "9_9") (pintype "passive"))
      (node (ref "JP2") (pin "2") (pinfunction "2_2") (pintype "passive"))
      (node (ref "JP2") (pin "9") (pinfunction "9_9") (pintype "passive"))
      (node (ref "JP3") (pin "21") (pinfunction "21_21") (pintype "passive"))
      (node (ref "JP3") (pin "23") (pinfunction "23_23") (pintype "passive"))
      (node (ref "JP3") (pin "25") (pinfunction "25_25") (pintype "passive"))
      (node (ref "JP4") (pin "21") (pinfunction "21_21") (pintype "passive"))
      (node (ref "JP4") (pin "23") (pinfunction "23_23") (pintype "passive"))
      (node (ref "JP4") (pin "25") (pinfunction "25_25") (pintype "passive"))
      (node (ref "JP5") (pin "21") (pinfunction "21_21") (pintype "passive"))
      (node (ref "JP5") (pin "23") (pinfunction "23_23") (pintype "passive"))
      (node (ref "JP5") (pin "25") (pinfunction "25_25") (pintype "passive"))
      (node (ref "JP6") (pin "21") (pinfunction "21_21") (pintype "passive"))
      (node (ref "JP6") (pin "23") (pinfunction "23_23") (pintype "passive"))
      (node (ref "JP6") (pin "25") (pinfunction "25_25") (pintype "passive"))
      (node (ref "SHIFT1") (pin "8") (pinfunction "GND_8") (pintype "power_in"))
      (node (ref "SHIFT2") (pin "8") (pinfunction "GND_8") (pintype "power_in"))
      (node (ref "SHIFT3") (pin "8") (pinfunction "GND_8") (pintype "power_in"))
      (node (ref "SHIFT4") (pin "8") (pinfunction "GND_8") (pintype "power_in"))
      (node (ref "SHIFT5") (pin "8") (pinfunction "GND_8") (pintype "power_in"))
      (node (ref "SHIFTOUTA") (pin "13") (pinfunction "G_13") (pintype "input"))
      (node (ref "SHIFTOUTA") (pin "8") (pinfunction "GND_8") (pintype "power_in"))
      (node (ref "SHIFTOUTB") (pin "13") (pinfunction "G_13") (pintype "input"))
      (node (ref "SHIFTOUTB") (pin "8") (pinfunction "GND_8") (pintype "power_in"))
      (node (ref "SHIFTOUTC") (pin "13") (pinfunction "G_13") (pintype "input"))
      (node (ref "SHIFTOUTC") (pin "8") (pinfunction "GND_8") (pintype "power_in"))
      (node (ref "SHIFTOUTD") (pin "13") (pinfunction "G_13") (pintype "input"))
      (node (ref "SHIFTOUTD") (pin "8") (pinfunction "GND_8") (pintype "power_in"))
      (node (ref "SHIFTOUTE") (pin "13") (pinfunction "G_13") (pintype "input"))
      (node (ref "SHIFTOUTE") (pin "8") (pinfunction "GND_8") (pintype "power_in"))
      (node (ref "U_OCA") (pin "9") (pinfunction "GND_9") (pintype "power_in"))
      (node (ref "U_OCA1") (pin "9") (pinfunction "GND_9") (pintype "power_in"))
      (node (ref "U_OCA2") (pin "9") (pinfunction "GND_9") (pintype "power_in"))
      (node (ref "U_OCA3") (pin "9") (pinfunction "GND_9") (pintype "power_in"))
      (node (ref "U_OCA4") (pin "9") (pinfunction "GND_9") (pintype "power_in"))
    )
    (net (code "85") (name "Net-(SHIFT1A-SER)") (class "Default")
      (node (ref "SHIFT1") (pin "10") (pinfunction "SER_10") (pintype "input"))
      (node (ref "SHIFT2") (pin "9") (pinfunction "QH_9") (pintype "output"))
    )
    (net (code "86") (name "Net-(SHIFT2A-SER)") (class "Default")
      (node (ref "SHIFT2") (pin "10") (pinfunction "SER_10") (pintype "input"))
      (node (ref "SHIFT3") (pin "9") (pinfunction "QH_9") (pintype "output"))
    )
    (net (code "87") (name "Net-(SHIFT3A-SER)") (class "Default")
      (node (ref "SHIFT3") (pin "10") (pinfunction "SER_10") (pintype "input"))
      (node (ref "SHIFT4") (pin "9") (pinfunction "QH_9") (pintype "output"))
    )
    (net (code "88") (name "Net-(SHIFT4A-SER)") (class "Default")
      (node (ref "SHIFT4") (pin "10") (pinfunction "SER_10") (pintype "input"))
      (node (ref "SHIFT5") (pin "9") (pinfunction "QH_9") (pintype "output"))
    )
    (net (code "89") (name "Net-(SHIFTOUTAA-QH*)") (class "Default")
      (node (ref "SHIFTOUTA") (pin "9") (pinfunction "QH*_9") (pintype "tri_state"))
      (node (ref "SHIFTOUTB") (pin "14") (pinfunction "SER_14") (pintype "input"))
    )
    (net (code "90") (name "Net-(SHIFTOUTBA-QH*)") (class "Default")
      (node (ref "SHIFTOUTB") (pin "9") (pinfunction "QH*_9") (pintype "tri_state"))
      (node (ref "SHIFTOUTC") (pin "14") (pinfunction "SER_14") (pintype "input"))
    )
    (net (code "91") (name "Net-(SHIFTOUTCA-QH*)") (class "Default")
      (node (ref "SHIFTOUTC") (pin "9") (pinfunction "QH*_9") (pintype "tri_state"))
      (node (ref "SHIFTOUTD") (pin "14") (pinfunction "SER_14") (pintype "input"))
    )
    (net (code "92") (name "Net-(SHIFTOUTDA-QH*)") (class "Default")
      (node (ref "SHIFTOUTD") (pin "9") (pinfunction "QH*_9") (pintype "tri_state"))
      (node (ref "SHIFTOUTE") (pin "14") (pinfunction "SER_14") (pintype "input"))
    )
    (net (code "93") (name "OUTA1") (class "Default")
      (node (ref "JP3") (pin "2") (pinfunction "2_2") (pintype "passive"))
      (node (ref "U_OCA") (pin "18") (pinfunction "OUT1_18") (pintype "open_collector"))
    )
    (net (code "94") (name "OUTA2") (class "Default")
      (node (ref "JP3") (pin "4") (pinfunction "4_4") (pintype "passive"))
      (node (ref "U_OCA") (pin "17") (pinfunction "OUT2_17") (pintype "open_collector"))
    )
    (net (code "95") (name "OUTA3") (class "Default")
      (node (ref "JP3") (pin "6") (pinfunction "6_6") (pintype "passive"))
      (node (ref "U_OCA") (pin "16") (pinfunction "OUT3_16") (pintype "open_collector"))
    )
    (net (code "96") (name "OUTA4") (class "Default")
      (node (ref "JP3") (pin "8") (pinfunction "8_8") (pintype "passive"))
      (node (ref "U_OCA") (pin "15") (pinfunction "OUT4_15") (pintype "open_collector"))
    )
    (net (code "97") (name "OUTA5") (class "Default")
      (node (ref "JP3") (pin "10") (pinfunction "10_10") (pintype "passive"))
      (node (ref "U_OCA") (pin "14") (pinfunction "OUT5_14") (pintype "open_collector"))
    )
    (net (code "98") (name "OUTA6") (class "Default")
      (node (ref "JP3") (pin "12") (pinfunction "12_12") (pintype "passive"))
      (node (ref "U_OCA") (pin "13") (pinfunction "OUT6_13") (pintype "open_collector"))
    )
    (net (code "99") (name "OUTA7") (class "Default")
      (node (ref "JP3") (pin "14") (pinfunction "14_14") (pintype "passive"))
      (node (ref "U_OCA") (pin "12") (pinfunction "OUT7_12") (pintype "open_collector"))
    )
    (net (code "100") (name "OUTA8") (class "Default")
      (node (ref "JP3") (pin "16") (pinfunction "16_16") (pintype "passive"))
      (node (ref "U_OCA") (pin "11") (pinfunction "OUT8_11") (pintype "open_collector"))
    )
    (net (code "101") (name "OUTB1") (class "Default")
      (node (ref "JP3") (pin "18") (pinfunction "18_18") (pintype "passive"))
      (node (ref "U_OCA1") (pin "18") (pinfunction "OUT1_18") (pintype "open_collector"))
    )
    (net (code "102") (name "OUTB2") (class "Default")
      (node (ref "JP3") (pin "20") (pinfunction "20_20") (pintype "passive"))
      (node (ref "U_OCA1") (pin "17") (pinfunction "OUT2_17") (pintype "open_collector"))
    )
    (net (code "103") (name "OUTB3") (class "Default")
      (node (ref "JP4") (pin "2") (pinfunction "2_2") (pintype "passive"))
      (node (ref "U_OCA1") (pin "16") (pinfunction "OUT3_16") (pintype "open_collector"))
    )
    (net (code "104") (name "OUTB4") (class "Default")
      (node (ref "JP4") (pin "4") (pinfunction "4_4") (pintype "passive"))
      (node (ref "U_OCA1") (pin "15") (pinfunction "OUT4_15") (pintype "open_collector"))
    )
    (net (code "105") (name "OUTB5") (class "Default")
      (node (ref "JP4") (pin "6") (pinfunction "6_6") (pintype "passive"))
      (node (ref "U_OCA1") (pin "14") (pinfunction "OUT5_14") (pintype "open_collector"))
    )
    (net (code "106") (name "OUTB6") (class "Default")
      (node (ref "JP4") (pin "8") (pinfunction "8_8") (pintype "passive"))
      (node (ref "U_OCA1") (pin "13") (pinfunction "OUT6_13") (pintype "open_collector"))
    )
    (net (code "107") (name "OUTB7") (class "Default")
      (node (ref "JP4") (pin "10") (pinfunction "10_10") (pintype "passive"))
      (node (ref "U_OCA1") (pin "12") (pinfunction "OUT7_12") (pintype "open_collector"))
    )
    (net (code "108") (name "OUTB8") (class "Default")
      (node (ref "JP4") (pin "12") (pinfunction "12_12") (pintype "passive"))
      (node (ref "U_OCA1") (pin "11") (pinfunction "OUT8_11") (pintype "open_collector"))
    )
    (net (code "109") (name "OUTC1") (class "Default")
      (node (ref "JP4") (pin "14") (pinfunction "14_14") (pintype "passive"))
      (node (ref "U_OCA2") (pin "18") (pinfunction "OUT1_18") (pintype "open_collector"))
    )
    (net (code "110") (name "OUTC2") (class "Default")
      (node (ref "JP4") (pin "16") (pinfunction "16_16") (pintype "passive"))
      (node (ref "U_OCA2") (pin "17") (pinfunction "OUT2_17") (pintype "open_collector"))
    )
    (net (code "111") (name "OUTC3") (class "Default")
      (node (ref "JP4") (pin "18") (pinfunction "18_18") (pintype "passive"))
      (node (ref "U_OCA2") (pin "16") (pinfunction "OUT3_16") (pintype "open_collector"))
    )
    (net (code "112") (name "OUTC4") (class "Default")
      (node (ref "JP4") (pin "20") (pinfunction "20_20") (pintype "passive"))
      (node (ref "U_OCA2") (pin "15") (pinfunction "OUT4_15") (pintype "open_collector"))
    )
    (net (code "113") (name "OUTC5") (class "Default")
      (node (ref "JP5") (pin "2") (pinfunction "2_2") (pintype "passive"))
      (node (ref "U_OCA2") (pin "14") (pinfunction "OUT5_14") (pintype "open_collector"))
    )
    (net (code "114") (name "OUTC6") (class "Default")
      (node (ref "JP5") (pin "4") (pinfunction "4_4") (pintype "passive"))
      (node (ref "U_OCA2") (pin "13") (pinfunction "OUT6_13") (pintype "open_collector"))
    )
    (net (code "115") (name "OUTC7") (class "Default")
      (node (ref "JP5") (pin "6") (pinfunction "6_6") (pintype "passive"))
      (node (ref "U_OCA2") (pin "12") (pinfunction "OUT7_12") (pintype "open_collector"))
    )
    (net (code "116") (name "OUTC8") (class "Default")
      (node (ref "JP5") (pin "8") (pinfunction "8_8") (pintype "passive"))
      (node (ref "U_OCA2") (pin "11") (pinfunction "OUT8_11") (pintype "open_collector"))
    )
    (net (code "117") (name "OUTD1") (class "Default")
      (node (ref "JP5") (pin "10") (pinfunction "10_10") (pintype "passive"))
      (node (ref "U_OCA3") (pin "18") (pinfunction "OUT1_18") (pintype "open_collector"))
    )
    (net (code "118") (name "OUTD2") (class "Default")
      (node (ref "JP5") (pin "12") (pinfunction "12_12") (pintype "passive"))
      (node (ref "U_OCA3") (pin "17") (pinfunction "OUT2_17") (pintype "open_collector"))
    )
    (net (code "119") (name "OUTD3") (class "Default")
      (node (ref "JP5") (pin "14") (pinfunction "14_14") (pintype "passive"))
      (node (ref "U_OCA3") (pin "16") (pinfunction "OUT3_16") (pintype "open_collector"))
    )
    (net (code "120") (name "OUTD4") (class "Default")
      (node (ref "JP5") (pin "16") (pinfunction "16_16") (pintype "passive"))
      (node (ref "U_OCA3") (pin "15") (pinfunction "OUT4_15") (pintype "open_collector"))
    )
    (net (code "121") (name "OUTD5") (class "Default")
      (node (ref "JP5") (pin "18") (pinfunction "18_18") (pintype "passive"))
      (node (ref "U_OCA3") (pin "14") (pinfunction "OUT5_14") (pintype "open_collector"))
    )
    (net (code "122") (name "OUTD6") (class "Default")
      (node (ref "JP5") (pin "20") (pinfunction "20_20") (pintype "passive"))
      (node (ref "U_OCA3") (pin "13") (pinfunction "OUT6_13") (pintype "open_collector"))
    )
    (net (code "123") (name "OUTD7") (class "Default")
      (node (ref "JP6") (pin "2") (pinfunction "2_2") (pintype "passive"))
      (node (ref "U_OCA3") (pin "12") (pinfunction "OUT7_12") (pintype "open_collector"))
    )
    (net (code "124") (name "OUTD8") (class "Default")
      (node (ref "JP6") (pin "4") (pinfunction "4_4") (pintype "passive"))
      (node (ref "U_OCA3") (pin "11") (pinfunction "OUT8_11") (pintype "open_collector"))
    )
    (net (code "125") (name "OUTE1") (class "Default")
      (node (ref "JP6") (pin "6") (pinfunction "6_6") (pintype "passive"))
      (node (ref "U_OCA4") (pin "18") (pinfunction "OUT1_18") (pintype "open_collector"))
    )
    (net (code "126") (name "OUTE2") (class "Default")
      (node (ref "JP6") (pin "8") (pinfunction "8_8") (pintype "passive"))
      (node (ref "U_OCA4") (pin "17") (pinfunction "OUT2_17") (pintype "open_collector"))
    )
    (net (code "127") (name "OUTE3") (class "Default")
      (node (ref "JP6") (pin "10") (pinfunction "10_10") (pintype "passive"))
      (node (ref "U_OCA4") (pin "16") (pinfunction "OUT3_16") (pintype "open_collector"))
    )
    (net (code "128") (name "OUTE4") (class "Default")
      (node (ref "JP6") (pin "12") (pinfunction "12_12") (pintype "passive"))
      (node (ref "U_OCA4") (pin "15") (pinfunction "OUT4_15") (pintype "open_collector"))
    )
    (net (code "129") (name "OUTE5") (class "Default")
      (node (ref "JP6") (pin "14") (pinfunction "14_14") (pintype "passive"))
      (node (ref "U_OCA4") (pin "14") (pinfunction "OUT5_14") (pintype "open_collector"))
    )
    (net (code "130") (name "OUTE6") (class "Default")
      (node (ref "JP6") (pin "16") (pinfunction "16_16") (pintype "passive"))
      (node (ref "U_OCA4") (pin "13") (pinfunction "OUT6_13") (pintype "open_collector"))
    )
    (net (code "131") (name "OUTE7") (class "Default")
      (node (ref "JP6") (pin "18") (pinfunction "18_18") (pintype "passive"))
      (node (ref "U_OCA4") (pin "12") (pinfunction "OUT7_12") (pintype "open_collector"))
    )
    (net (code "132") (name "OUTE8") (class "Default")
      (node (ref "JP6") (pin "20") (pinfunction "20_20") (pintype "passive"))
      (node (ref "U_OCA4") (pin "11") (pinfunction "OUT8_11") (pintype "open_collector"))
    )
    (net (code "133") (name "PL") (class "Default")
      (node (ref "JP1") (pin "7") (pinfunction "7_7") (pintype "passive"))
      (node (ref "JP2") (pin "7") (pinfunction "7_7") (pintype "passive"))
      (node (ref "SHIFT1") (pin "1") (pinfunction "SH/~{LD}_1") (pintype "input"))
      (node (ref "SHIFT2") (pin "1") (pinfunction "SH/~{LD}_1") (pintype "input"))
      (node (ref "SHIFT3") (pin "1") (pinfunction "SH/~{LD}_1") (pintype "input"))
      (node (ref "SHIFT4") (pin "1") (pinfunction "SH/~{LD}_1") (pintype "input"))
      (node (ref "SHIFT5") (pin "1") (pinfunction "SH/~{LD}_1") (pintype "input"))
    )
    (net (code "134") (name "Q7") (class "Default")
      (node (ref "JP1") (pin "1") (pinfunction "1_1") (pintype "passive"))
      (node (ref "SHIFT1") (pin "9") (pinfunction "QH_9") (pintype "output"))
    )
    (net (code "135") (name "Q7_2") (class "Default")
      (node (ref "JP2") (pin "1") (pinfunction "1_1") (pintype "passive"))
      (node (ref "SHIFT5") (pin "10") (pinfunction "SER_10") (pintype "input"))
    )
    (net (code "136") (name "SHCP") (class "Default")
      (node (ref "JP1") (pin "8") (pinfunction "8_8") (pintype "passive"))
      (node (ref "JP2") (pin "8") (pinfunction "8_8") (pintype "passive"))
      (node (ref "SHIFTOUTA") (pin "11") (pinfunction "SCK_11") (pintype "input"))
      (node (ref "SHIFTOUTB") (pin "11") (pinfunction "SCK_11") (pintype "input"))
      (node (ref "SHIFTOUTC") (pin "11") (pinfunction "SCK_11") (pintype "input"))
      (node (ref "SHIFTOUTD") (pin "11") (pinfunction "SCK_11") (pintype "input"))
      (node (ref "SHIFTOUTE") (pin "11") (pinfunction "SCK_11") (pintype "input"))
    )
    (net (code "137") (name "SR_DS") (class "Default")
      (node (ref "JP1") (pin "4") (pinfunction "4_4") (pintype "passive"))
      (node (ref "SHIFTOUTA") (pin "14") (pinfunction "SER_14") (pintype "input"))
    )
    (net (code "138") (name "SR_DS_2") (class "Default")
      (node (ref "JP2") (pin "4") (pinfunction "4_4") (pintype "passive"))
      (node (ref "SHIFTOUTE") (pin "9") (pinfunction "QH*_9") (pintype "tri_state"))
    )
    (net (code "139") (name "SR_RST") (class "Default")
      (node (ref "JP1") (pin "10") (pinfunction "10_10") (pintype "passive"))
      (node (ref "JP2") (pin "10") (pinfunction "10_10") (pintype "passive"))
      (node (ref "SHIFTOUTA") (pin "10") (pinfunction "SCL_10") (pintype "input"))
      (node (ref "SHIFTOUTB") (pin "10") (pinfunction "SCL_10") (pintype "input"))
      (node (ref "SHIFTOUTC") (pin "10") (pinfunction "SCL_10") (pintype "input"))
      (node (ref "SHIFTOUTD") (pin "10") (pinfunction "SCL_10") (pintype "input"))
      (node (ref "SHIFTOUTE") (pin "10") (pinfunction "SCL_10") (pintype "input"))
    )
    (net (code "140") (name "STCP") (class "Default")
      (node (ref "JP1") (pin "6") (pinfunction "6_6") (pintype "passive"))
      (node (ref "JP2") (pin "6") (pinfunction "6_6") (pintype "passive"))
      (node (ref "SHIFTOUTA") (pin "12") (pinfunction "RCK_12") (pintype "input"))
      (node (ref "SHIFTOUTB") (pin "12") (pinfunction "RCK_12") (pintype "input"))
      (node (ref "SHIFTOUTC") (pin "12") (pinfunction "RCK_12") (pintype "input"))
      (node (ref "SHIFTOUTD") (pin "12") (pinfunction "RCK_12") (pintype "input"))
      (node (ref "SHIFTOUTE") (pin "12") (pinfunction "RCK_12") (pintype "input"))
    )
    (net (code "141") (name "VCC") (class "Default")
      (node (ref "C1") (pin "1") (pinfunction "1_1") (pintype "passive"))
      (node (ref "C2") (pin "1") (pinfunction "1_1") (pintype "passive"))
      (node (ref "C3") (pin "1") (pinfunction "1_1") (pintype "passive"))
      (node (ref "C4") (pin "1") (pinfunction "1_1") (pintype "passive"))
      (node (ref "C5") (pin "1") (pinfunction "1_1") (pintype "passive"))
      (node (ref "J1") (pin "1") (pinfunction "1_1") (pintype "bidirectional"))
      (node (ref "J2") (pin "4") (pinfunction "4_4") (pintype "bidirectional"))
      (node (ref "R1") (pin "2") (pinfunction "2_2") (pintype "passive"))
      (node (ref "R2") (pin "2") (pinfunction "2_2") (pintype "passive"))
      (node (ref "R3") (pin "2") (pinfunction "2_2") (pintype "passive"))
      (node (ref "R4") (pin "2") (pinfunction "2_2") (pintype "passive"))
      (node (ref "R5") (pin "2") (pinfunction "2_2") (pintype "passive"))
      (node (ref "R6") (pin "2") (pinfunction "2_2") (pintype "passive"))
      (node (ref "R7") (pin "2") (pinfunction "2_2") (pintype "passive"))
      (node (ref "R8") (pin "2") (pinfunction "2_2") (pintype "passive"))
      (node (ref "RN1") (pin "1") (pinfunction "1_1") (pintype "passive"))
      (node (ref "RN2") (pin "1") (pinfunction "1_1") (pintype "passive"))
      (node (ref "RN4") (pin "1") (pinfunction "1_1") (pintype "passive"))
      (node (ref "RN5") (pin "1") (pinfunction "1_1") (pintype "passive"))
      (node (ref "SHIFT1") (pin "16") (pinfunction "VCC_16") (pintype "power_in"))
      (node (ref "SHIFT2") (pin "16") (pinfunction "VCC_16") (pintype "power_in"))
      (node (ref "SHIFT3") (pin "16") (pinfunction "VCC_16") (pintype "power_in"))
      (node (ref "SHIFT4") (pin "16") (pinfunction "VCC_16") (pintype "power_in"))
      (node (ref "SHIFT5") (pin "16") (pinfunction "VCC_16") (pintype "power_in"))
      (node (ref "SHIFTOUTA") (pin "16") (pinfunction "VCC_16") (pintype "power_in"))
      (node (ref "SHIFTOUTB") (pin "16") (pinfunction "VCC_16") (pintype "power_in"))
      (node (ref "SHIFTOUTC") (pin "16") (pinfunction "VCC_16") (pintype "power_in"))
      (node (ref "SHIFTOUTD") (pin "16") (pinfunction "VCC_16") (pintype "power_in"))
      (node (ref "SHIFTOUTE") (pin "16") (pinfunction "VCC_16") (pintype "power_in"))
    )
    (net (code "142") (name "unconnected-(SHIFT1A-~{QH}-Pad7)") (class "Default")
      (node (ref "SHIFT1") (pin "7") (pinfunction "~{QH}_7") (pintype "output"))
    )
    (net (code "143") (name "unconnected-(SHIFT2A-~{QH}-Pad7)") (class "Default")
      (node (ref "SHIFT2") (pin "7") (pinfunction "~{QH}_7") (pintype "output"))
    )
    (net (code "144") (name "unconnected-(SHIFT3A-~{QH}-Pad7)") (class "Default")
      (node (ref "SHIFT3") (pin "7") (pinfunction "~{QH}_7") (pintype "output"))
    )
    (net (code "145") (name "unconnected-(SHIFT4A-~{QH}-Pad7)") (class "Default")
      (node (ref "SHIFT4") (pin "7") (pinfunction "~{QH}_7") (pintype "output"))
    )
    (net (code "146") (name "unconnected-(SHIFT5A-~{QH}-Pad7)") (class "Default")
      (node (ref "SHIFT5") (pin "7") (pinfunction "~{QH}_7") (pintype "output"))
    )
  )
)
